# picoKey_2304.net
KiCad netlist of a schematic drawn in EAGLE
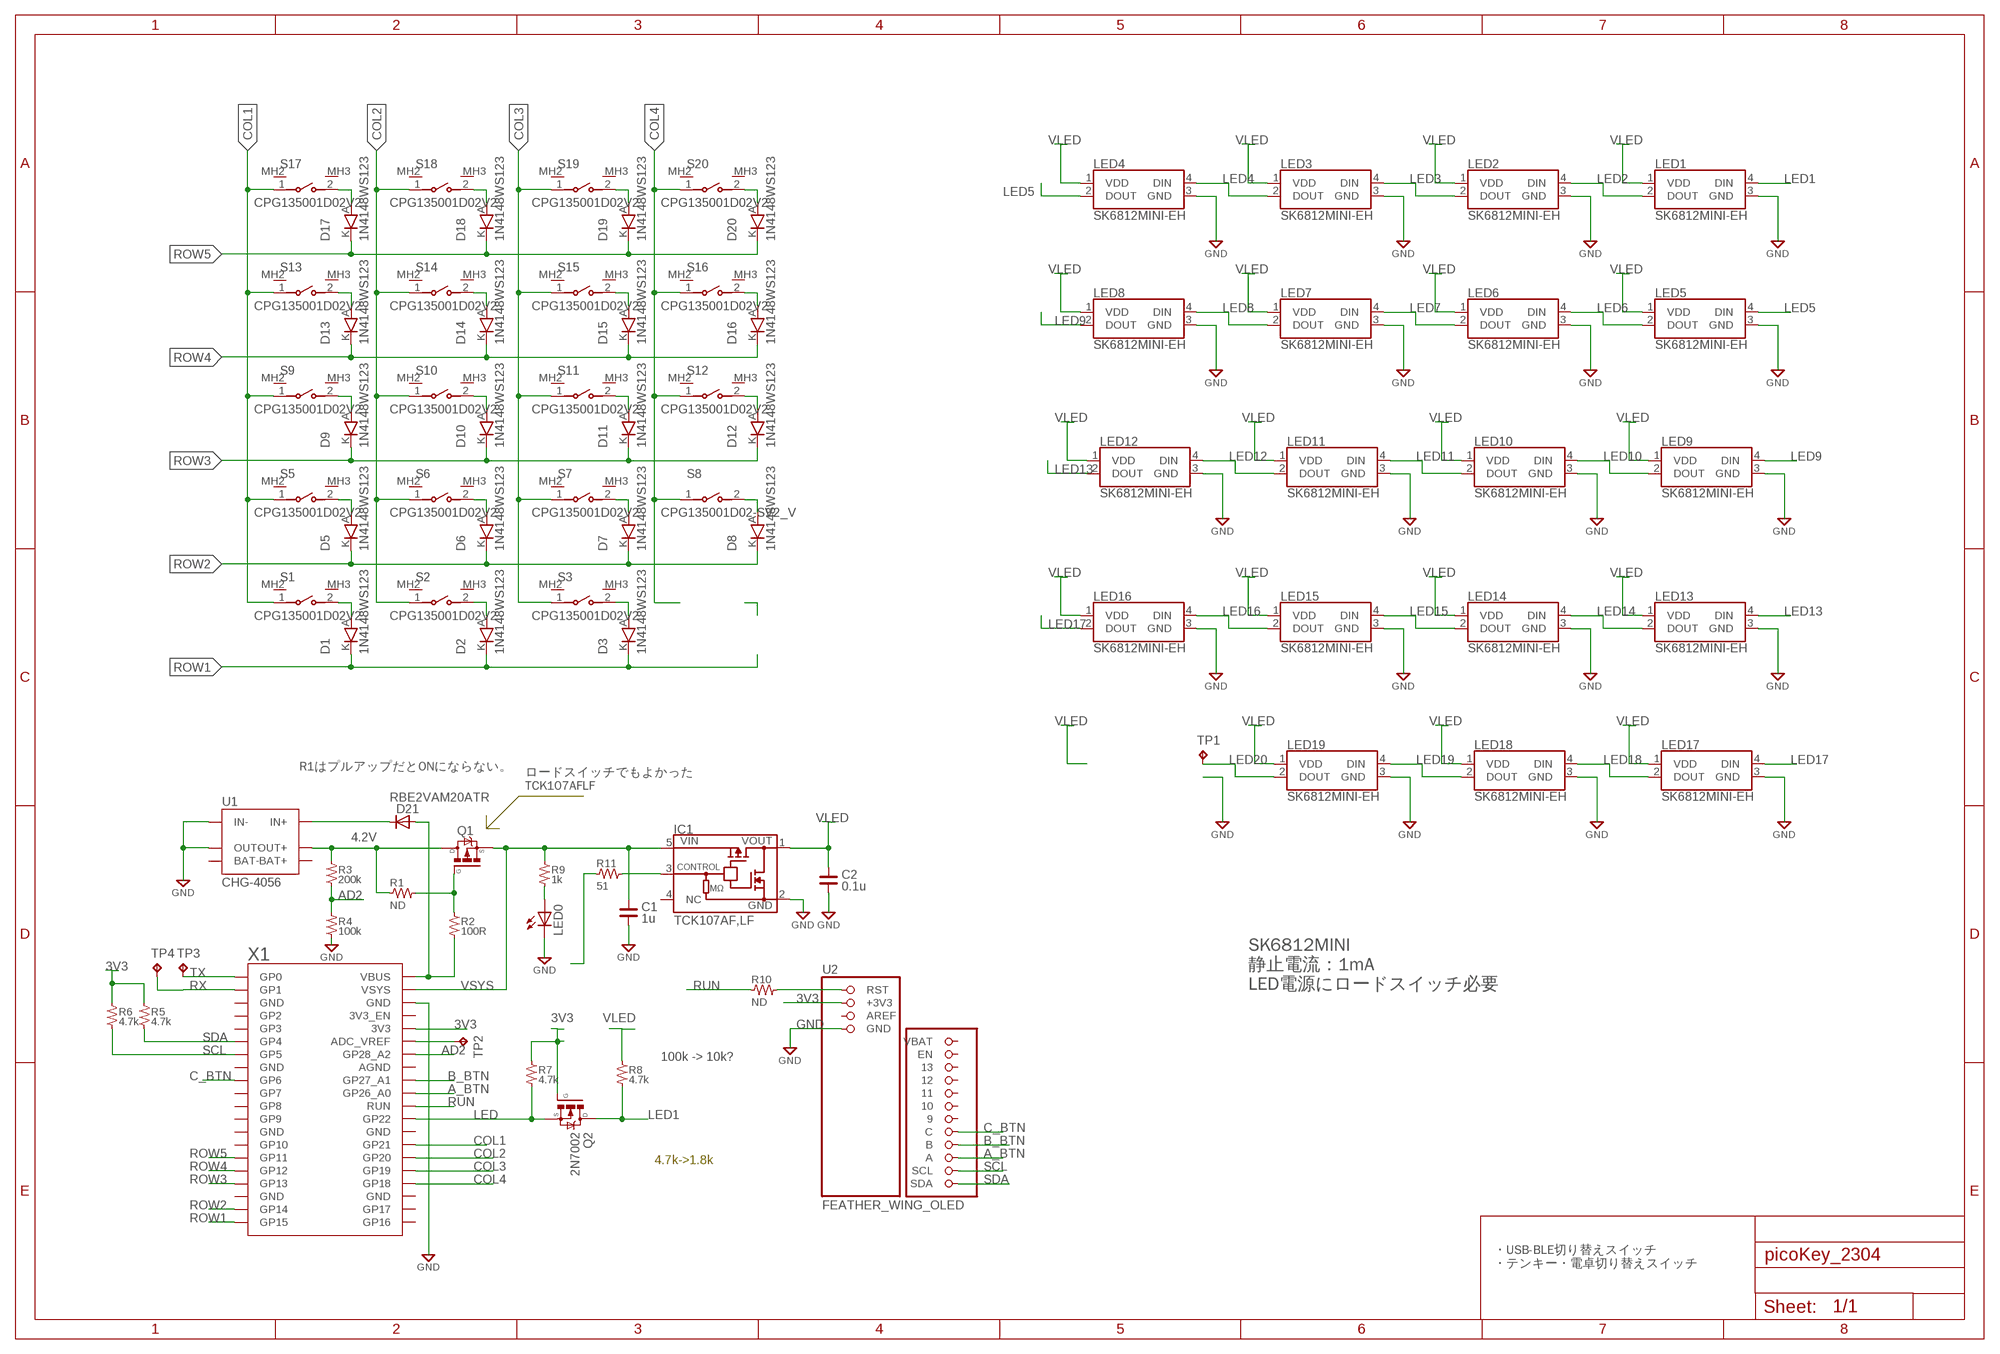
[diagram p0: schematic, sheet 1]

(export (version "E")
  (design (tool "Eeschema 10.0.6"))
  (components
    (comp (ref "C1")
      (value "1u")
      (footprint "eagle-import:C0603")
      (libsource (lib "eagle-import") (part "C_0603"))
    )
    (comp (ref "C2")
      (value "0.1u")
      (footprint "eagle-import:C0603")
      (libsource (lib "eagle-import") (part "C_0603"))
    )
    (comp (ref "D1")
      (value "1N4148WS123")
      (footprint "eagle-import:SOD-123")
      (libsource (lib "eagle-import") (part "1N4148WS123"))
    )
    (comp (ref "D2")
      (value "1N4148WS123")
      (footprint "eagle-import:SOD-123")
      (libsource (lib "eagle-import") (part "1N4148WS123"))
    )
    (comp (ref "D3")
      (value "1N4148WS123")
      (footprint "eagle-import:SOD-123")
      (libsource (lib "eagle-import") (part "1N4148WS123"))
    )
    (comp (ref "D5")
      (value "1N4148WS123")
      (footprint "eagle-import:SOD-123")
      (libsource (lib "eagle-import") (part "1N4148WS123"))
    )
    (comp (ref "D6")
      (value "1N4148WS123")
      (footprint "eagle-import:SOD-123")
      (libsource (lib "eagle-import") (part "1N4148WS123"))
    )
    (comp (ref "D7")
      (value "1N4148WS123")
      (footprint "eagle-import:SOD-123")
      (libsource (lib "eagle-import") (part "1N4148WS123"))
    )
    (comp (ref "D8")
      (value "1N4148WS123")
      (footprint "eagle-import:SOD-123")
      (libsource (lib "eagle-import") (part "1N4148WS123"))
    )
    (comp (ref "D9")
      (value "1N4148WS123")
      (footprint "eagle-import:SOD-123")
      (libsource (lib "eagle-import") (part "1N4148WS123"))
    )
    (comp (ref "D10")
      (value "1N4148WS123")
      (footprint "eagle-import:SOD-123")
      (libsource (lib "eagle-import") (part "1N4148WS123"))
    )
    (comp (ref "D11")
      (value "1N4148WS123")
      (footprint "eagle-import:SOD-123")
      (libsource (lib "eagle-import") (part "1N4148WS123"))
    )
    (comp (ref "D12")
      (value "1N4148WS123")
      (footprint "eagle-import:SOD-123")
      (libsource (lib "eagle-import") (part "1N4148WS123"))
    )
    (comp (ref "D13")
      (value "1N4148WS123")
      (footprint "eagle-import:SOD-123")
      (libsource (lib "eagle-import") (part "1N4148WS123"))
    )
    (comp (ref "D14")
      (value "1N4148WS123")
      (footprint "eagle-import:SOD-123")
      (libsource (lib "eagle-import") (part "1N4148WS123"))
    )
    (comp (ref "D15")
      (value "1N4148WS123")
      (footprint "eagle-import:SOD-123")
      (libsource (lib "eagle-import") (part "1N4148WS123"))
    )
    (comp (ref "D16")
      (value "1N4148WS123")
      (footprint "eagle-import:SOD-123")
      (libsource (lib "eagle-import") (part "1N4148WS123"))
    )
    (comp (ref "D17")
      (value "1N4148WS123")
      (footprint "eagle-import:SOD-123")
      (libsource (lib "eagle-import") (part "1N4148WS123"))
    )
    (comp (ref "D18")
      (value "1N4148WS123")
      (footprint "eagle-import:SOD-123")
      (libsource (lib "eagle-import") (part "1N4148WS123"))
    )
    (comp (ref "D19")
      (value "1N4148WS123")
      (footprint "eagle-import:SOD-123")
      (libsource (lib "eagle-import") (part "1N4148WS123"))
    )
    (comp (ref "D20")
      (value "1N4148WS123")
      (footprint "eagle-import:SOD-123")
      (libsource (lib "eagle-import") (part "1N4148WS123"))
    )
    (comp (ref "D21")
      (value "RBE2VAM20ATR")
      (footprint "eagle-import:SOD-123")
      (libsource (lib "eagle-import") (part "DIODE123"))
    )
    (comp (ref "IC1")
      (value "TCK107AF,LF")
      (footprint "eagle-import:SMV_1")
      (fields
        (field (name "ARROW_PART_NUMBER") "TCK106AF,LF")
        (field (name "MOUSER_PART_NUMBER") "757-TCK106AFLF")
      )
      (libsource (lib "eagle-import") (part "TCK107AF,LF"))
    )
    (comp (ref "LED0")
      (value "LEDCHIP-LED0603")
      (footprint "eagle-import:CHIP-LED0603")
      (libsource (lib "eagle-import") (part "LEDCHIP-LED0603"))
    )
    (comp (ref "LED1")
      (value "SK6812MINI-EH")
      (footprint "eagle-import:SK6812MINIE-H")
      (libsource (lib "eagle-import") (part "SK6812MINI-EH"))
    )
    (comp (ref "LED2")
      (value "SK6812MINI-EH")
      (footprint "eagle-import:SK6812MINIE-H")
      (libsource (lib "eagle-import") (part "SK6812MINI-EH"))
    )
    (comp (ref "LED3")
      (value "SK6812MINI-EH")
      (footprint "eagle-import:SK6812MINIE-H")
      (libsource (lib "eagle-import") (part "SK6812MINI-EH"))
    )
    (comp (ref "LED4")
      (value "SK6812MINI-EH")
      (footprint "eagle-import:SK6812MINIE-H")
      (libsource (lib "eagle-import") (part "SK6812MINI-EH"))
    )
    (comp (ref "LED5")
      (value "SK6812MINI-EH")
      (footprint "eagle-import:SK6812MINIE-H")
      (libsource (lib "eagle-import") (part "SK6812MINI-EH"))
    )
    (comp (ref "LED6")
      (value "SK6812MINI-EH")
      (footprint "eagle-import:SK6812MINIE-H")
      (libsource (lib "eagle-import") (part "SK6812MINI-EH"))
    )
    (comp (ref "LED7")
      (value "SK6812MINI-EH")
      (footprint "eagle-import:SK6812MINIE-H")
      (libsource (lib "eagle-import") (part "SK6812MINI-EH"))
    )
    (comp (ref "LED8")
      (value "SK6812MINI-EH")
      (footprint "eagle-import:SK6812MINIE-H")
      (libsource (lib "eagle-import") (part "SK6812MINI-EH"))
    )
    (comp (ref "LED9")
      (value "SK6812MINI-EH")
      (footprint "eagle-import:SK6812MINIE-H")
      (libsource (lib "eagle-import") (part "SK6812MINI-EH"))
    )
    (comp (ref "LED10")
      (value "SK6812MINI-EH")
      (footprint "eagle-import:SK6812MINIE-H")
      (libsource (lib "eagle-import") (part "SK6812MINI-EH"))
    )
    (comp (ref "LED11")
      (value "SK6812MINI-EH")
      (footprint "eagle-import:SK6812MINIE-H")
      (libsource (lib "eagle-import") (part "SK6812MINI-EH"))
    )
    (comp (ref "LED12")
      (value "SK6812MINI-EH")
      (footprint "eagle-import:SK6812MINIE-H")
      (libsource (lib "eagle-import") (part "SK6812MINI-EH"))
    )
    (comp (ref "LED13")
      (value "SK6812MINI-EH")
      (footprint "eagle-import:SK6812MINIE-H")
      (libsource (lib "eagle-import") (part "SK6812MINI-EH"))
    )
    (comp (ref "LED14")
      (value "SK6812MINI-EH")
      (footprint "eagle-import:SK6812MINIE-H")
      (libsource (lib "eagle-import") (part "SK6812MINI-EH"))
    )
    (comp (ref "LED15")
      (value "SK6812MINI-EH")
      (footprint "eagle-import:SK6812MINIE-H")
      (libsource (lib "eagle-import") (part "SK6812MINI-EH"))
    )
    (comp (ref "LED16")
      (value "SK6812MINI-EH")
      (footprint "eagle-import:SK6812MINIE-H")
      (libsource (lib "eagle-import") (part "SK6812MINI-EH"))
    )
    (comp (ref "LED17")
      (value "SK6812MINI-EH")
      (footprint "eagle-import:SK6812MINIE-H")
      (libsource (lib "eagle-import") (part "SK6812MINI-EH"))
    )
    (comp (ref "LED18")
      (value "SK6812MINI-EH")
      (footprint "eagle-import:SK6812MINIE-H")
      (libsource (lib "eagle-import") (part "SK6812MINI-EH"))
    )
    (comp (ref "LED19")
      (value "SK6812MINI-EH")
      (footprint "eagle-import:SK6812MINIE-H")
      (libsource (lib "eagle-import") (part "SK6812MINI-EH"))
    )
    (comp (ref "Q1")
      (value "MOSFET-P")
      (footprint "eagle-import:SOT-23")
      (libsource (lib "eagle-import") (part "MOSFET-P"))
    )
    (comp (ref "Q2")
      (value "2N7002")
      (footprint "eagle-import:SOT-23")
      (libsource (lib "eagle-import") (part "MOSFET-NSOT-23"))
    )
    (comp (ref "R1")
      (value "ND")
      (footprint "eagle-import:R0603")
      (libsource (lib "eagle-import") (part "R_0603"))
    )
    (comp (ref "R2")
      (value "100R")
      (footprint "eagle-import:R0603")
      (libsource (lib "eagle-import") (part "R_0603"))
    )
    (comp (ref "R3")
      (value "200k")
      (footprint "eagle-import:R0603")
      (libsource (lib "eagle-import") (part "R_0603"))
    )
    (comp (ref "R4")
      (value "100k")
      (footprint "eagle-import:R0603")
      (libsource (lib "eagle-import") (part "R_0603"))
    )
    (comp (ref "R5")
      (value "4.7k")
      (footprint "eagle-import:R0603")
      (libsource (lib "eagle-import") (part "R_0603"))
    )
    (comp (ref "R6")
      (value "4.7k")
      (footprint "eagle-import:R0603")
      (libsource (lib "eagle-import") (part "R_0603"))
    )
    (comp (ref "R7")
      (value "4.7k")
      (footprint "eagle-import:R0603")
      (libsource (lib "eagle-import") (part "R_0603"))
    )
    (comp (ref "R8")
      (value "4.7k")
      (footprint "eagle-import:R0603")
      (libsource (lib "eagle-import") (part "R_0603"))
    )
    (comp (ref "R9")
      (value "1k")
      (footprint "eagle-import:R0603")
      (libsource (lib "eagle-import") (part "R_0603"))
    )
    (comp (ref "R10")
      (value "ND")
      (footprint "eagle-import:R0603")
      (libsource (lib "eagle-import") (part "R_0603"))
    )
    (comp (ref "R11")
      (value "51")
      (footprint "eagle-import:R0603")
      (libsource (lib "eagle-import") (part "R_0603"))
    )
    (comp (ref "S1")
      (value "CPG135001D02V2")
      (footprint "eagle-import:KAILH_CHOC_V2")
      (libsource (lib "eagle-import") (part "CPG135001D02V2"))
    )
    (comp (ref "S2")
      (value "CPG135001D02V2")
      (footprint "eagle-import:KAILH_CHOC_V2")
      (libsource (lib "eagle-import") (part "CPG135001D02V2"))
    )
    (comp (ref "S3")
      (value "CPG135001D02V2")
      (footprint "eagle-import:KAILH_CHOC_V2")
      (libsource (lib "eagle-import") (part "CPG135001D02V2"))
    )
    (comp (ref "S5")
      (value "CPG135001D02V2")
      (footprint "eagle-import:KAILH_CHOC_V2")
      (libsource (lib "eagle-import") (part "CPG135001D02V2"))
    )
    (comp (ref "S6")
      (value "CPG135001D02V2")
      (footprint "eagle-import:KAILH_CHOC_V2")
      (libsource (lib "eagle-import") (part "CPG135001D02V2"))
    )
    (comp (ref "S7")
      (value "CPG135001D02V2")
      (footprint "eagle-import:KAILH_CHOC_V2")
      (libsource (lib "eagle-import") (part "CPG135001D02V2"))
    )
    (comp (ref "S8")
      (value "CPG135001D02-SV2_V")
      (footprint "eagle-import:KAILH_CHOC_V2_V")
      (libsource (lib "eagle-import") (part "CPG135001D02-SV2_V"))
    )
    (comp (ref "S9")
      (value "CPG135001D02V2")
      (footprint "eagle-import:KAILH_CHOC_V2")
      (libsource (lib "eagle-import") (part "CPG135001D02V2"))
    )
    (comp (ref "S10")
      (value "CPG135001D02V2")
      (footprint "eagle-import:KAILH_CHOC_V2")
      (libsource (lib "eagle-import") (part "CPG135001D02V2"))
    )
    (comp (ref "S11")
      (value "CPG135001D02V2")
      (footprint "eagle-import:KAILH_CHOC_V2")
      (libsource (lib "eagle-import") (part "CPG135001D02V2"))
    )
    (comp (ref "S12")
      (value "CPG135001D02V2")
      (footprint "eagle-import:KAILH_CHOC_V2")
      (libsource (lib "eagle-import") (part "CPG135001D02V2"))
    )
    (comp (ref "S13")
      (value "CPG135001D02V2")
      (footprint "eagle-import:KAILH_CHOC_V2")
      (libsource (lib "eagle-import") (part "CPG135001D02V2"))
    )
    (comp (ref "S14")
      (value "CPG135001D02V2")
      (footprint "eagle-import:KAILH_CHOC_V2")
      (libsource (lib "eagle-import") (part "CPG135001D02V2"))
    )
    (comp (ref "S15")
      (value "CPG135001D02V2")
      (footprint "eagle-import:KAILH_CHOC_V2")
      (libsource (lib "eagle-import") (part "CPG135001D02V2"))
    )
    (comp (ref "S16")
      (value "CPG135001D02V2")
      (footprint "eagle-import:KAILH_CHOC_V2")
      (libsource (lib "eagle-import") (part "CPG135001D02V2"))
    )
    (comp (ref "S17")
      (value "CPG135001D02V2")
      (footprint "eagle-import:KAILH_CHOC_V2")
      (libsource (lib "eagle-import") (part "CPG135001D02V2"))
    )
    (comp (ref "S18")
      (value "CPG135001D02V2")
      (footprint "eagle-import:KAILH_CHOC_V2")
      (libsource (lib "eagle-import") (part "CPG135001D02V2"))
    )
    (comp (ref "S19")
      (value "CPG135001D02V2")
      (footprint "eagle-import:KAILH_CHOC_V2")
      (libsource (lib "eagle-import") (part "CPG135001D02V2"))
    )
    (comp (ref "S20")
      (value "CPG135001D02V2")
      (footprint "eagle-import:KAILH_CHOC_V2")
      (libsource (lib "eagle-import") (part "CPG135001D02V2"))
    )
    (comp (ref "TP1")
      (value "TPTP06R")
      (footprint "eagle-import:TP06R")
      (libsource (lib "eagle-import") (part "TPTP06R"))
    )
    (comp (ref "TP2")
      (value "TPTP06R")
      (footprint "eagle-import:TP06R")
      (libsource (lib "eagle-import") (part "TPTP06R"))
    )
    (comp (ref "TP3")
      (value "TPTP06R")
      (footprint "eagle-import:TP06R")
      (libsource (lib "eagle-import") (part "TPTP06R"))
    )
    (comp (ref "TP4")
      (value "TPTP06R")
      (footprint "eagle-import:TP06R")
      (libsource (lib "eagle-import") (part "TPTP06R"))
    )
    (comp (ref "U1")
      (value "CHG-4056")
      (footprint "eagle-import:CHG-4056")
      (libsource (lib "eagle-import") (part "CHG-4056"))
    )
    (comp (ref "U2")
      (value "FEATHER_WING_OLED")
      (footprint "eagle-import:FEATHER_WING_OLED")
      (libsource (lib "eagle-import") (part "FEATHER_WING_OLED"))
    )
    (comp (ref "X1")
      (value "RASPBERRYPI_PICO_RPI_PICO_MY-MY")
      (footprint "eagle-import:RASPBERRYPI_PICO_RPI_PICO_MY")
      (libsource (lib "eagle-import") (part "RASPBERRYPI_PICO_RPI_PICO_MY-MY"))
    )
  )
  (nets
    (net (code "1") (name "/3V3") (class "Default")
      (node (ref "Q2") (pin "3") (pinfunction "G_3") (pintype "passive"))
      (node (ref "R5") (pin "2") (pinfunction "2_2") (pintype "passive"))
      (node (ref "R6") (pin "2") (pinfunction "2_2") (pintype "passive"))
      (node (ref "R7") (pin "1") (pinfunction "1_1") (pintype "passive"))
      (node (ref "U2") (pin "15") (pinfunction "+3V3_15") (pintype "passive"))
      (node (ref "X1") (pin "3V3") (pinfunction "3V3_3V3") (pintype "bidirectional"))
    )
    (net (code "2") (name "/4.2V") (class "Default")
      (node (ref "Q1") (pin "2") (pinfunction "D_2") (pintype "passive"))
      (node (ref "R1") (pin "1") (pinfunction "1_1") (pintype "passive"))
      (node (ref "R3") (pin "2") (pinfunction "2_2") (pintype "passive"))
      (node (ref "U1") (pin "OUT+") (pinfunction "OUT+_OUT+") (pintype "bidirectional"))
    )
    (net (code "3") (name "/AD2") (class "Default")
      (node (ref "R3") (pin "1") (pinfunction "1_1") (pintype "passive"))
      (node (ref "R4") (pin "2") (pinfunction "2_2") (pintype "passive"))
      (node (ref "X1") (pin "GP28_A2") (pinfunction "GP28_A2_GP28_A2") (pintype "bidirectional"))
    )
    (net (code "4") (name "/A_BTN") (class "Default")
      (node (ref "U2") (pin "26") (pinfunction "A_26") (pintype "passive"))
      (node (ref "X1") (pin "GP26_A0") (pinfunction "GP26_A0_GP26_A0") (pintype "bidirectional"))
    )
    (net (code "5") (name "/B_BTN") (class "Default")
      (node (ref "U2") (pin "25") (pinfunction "B_25") (pintype "passive"))
      (node (ref "X1") (pin "GP27_A1") (pinfunction "GP27_A1_GP27_A1") (pintype "bidirectional"))
    )
    (net (code "6") (name "/C_BTN") (class "Default")
      (node (ref "U2") (pin "24") (pinfunction "C_24") (pintype "passive"))
      (node (ref "X1") (pin "GP6") (pinfunction "GP6_GP6") (pintype "bidirectional"))
    )
    (net (code "7") (name "/LED") (class "Default")
      (node (ref "Q2") (pin "1") (pinfunction "S_1") (pintype "passive"))
      (node (ref "R7") (pin "2") (pinfunction "2_2") (pintype "passive"))
      (node (ref "X1") (pin "GP22") (pinfunction "GP22_GP22") (pintype "bidirectional"))
    )
    (net (code "8") (name "/LED1") (class "Default")
      (node (ref "LED1") (pin "4") (pinfunction "DIN_4") (pintype "bidirectional"))
      (node (ref "Q2") (pin "2") (pinfunction "D_2") (pintype "passive"))
      (node (ref "R8") (pin "2") (pinfunction "2_2") (pintype "passive"))
    )
    (net (code "9") (name "/LED2") (class "Default")
      (node (ref "LED1") (pin "2") (pinfunction "DOUT_2") (pintype "bidirectional"))
      (node (ref "LED2") (pin "4") (pinfunction "DIN_4") (pintype "bidirectional"))
    )
    (net (code "10") (name "/LED3") (class "Default")
      (node (ref "LED2") (pin "2") (pinfunction "DOUT_2") (pintype "bidirectional"))
      (node (ref "LED3") (pin "4") (pinfunction "DIN_4") (pintype "bidirectional"))
    )
    (net (code "11") (name "/LED4") (class "Default")
      (node (ref "LED3") (pin "2") (pinfunction "DOUT_2") (pintype "bidirectional"))
      (node (ref "LED4") (pin "4") (pinfunction "DIN_4") (pintype "bidirectional"))
    )
    (net (code "12") (name "/LED5") (class "Default")
      (node (ref "LED4") (pin "2") (pinfunction "DOUT_2") (pintype "bidirectional"))
      (node (ref "LED5") (pin "4") (pinfunction "DIN_4") (pintype "bidirectional"))
    )
    (net (code "13") (name "/LED6") (class "Default")
      (node (ref "LED5") (pin "2") (pinfunction "DOUT_2") (pintype "bidirectional"))
      (node (ref "LED6") (pin "4") (pinfunction "DIN_4") (pintype "bidirectional"))
    )
    (net (code "14") (name "/LED7") (class "Default")
      (node (ref "LED6") (pin "2") (pinfunction "DOUT_2") (pintype "bidirectional"))
      (node (ref "LED7") (pin "4") (pinfunction "DIN_4") (pintype "bidirectional"))
    )
    (net (code "15") (name "/LED8") (class "Default")
      (node (ref "LED7") (pin "2") (pinfunction "DOUT_2") (pintype "bidirectional"))
      (node (ref "LED8") (pin "4") (pinfunction "DIN_4") (pintype "bidirectional"))
    )
    (net (code "16") (name "/LED9") (class "Default")
      (node (ref "LED8") (pin "2") (pinfunction "DOUT_2") (pintype "bidirectional"))
      (node (ref "LED9") (pin "4") (pinfunction "DIN_4") (pintype "bidirectional"))
    )
    (net (code "17") (name "/LED10") (class "Default")
      (node (ref "LED10") (pin "4") (pinfunction "DIN_4") (pintype "bidirectional"))
      (node (ref "LED9") (pin "2") (pinfunction "DOUT_2") (pintype "bidirectional"))
    )
    (net (code "18") (name "/LED11") (class "Default")
      (node (ref "LED10") (pin "2") (pinfunction "DOUT_2") (pintype "bidirectional"))
      (node (ref "LED11") (pin "4") (pinfunction "DIN_4") (pintype "bidirectional"))
    )
    (net (code "19") (name "/LED12") (class "Default")
      (node (ref "LED11") (pin "2") (pinfunction "DOUT_2") (pintype "bidirectional"))
      (node (ref "LED12") (pin "4") (pinfunction "DIN_4") (pintype "bidirectional"))
    )
    (net (code "20") (name "/LED13") (class "Default")
      (node (ref "LED12") (pin "2") (pinfunction "DOUT_2") (pintype "bidirectional"))
      (node (ref "LED13") (pin "4") (pinfunction "DIN_4") (pintype "bidirectional"))
    )
    (net (code "21") (name "/LED14") (class "Default")
      (node (ref "LED13") (pin "2") (pinfunction "DOUT_2") (pintype "bidirectional"))
      (node (ref "LED14") (pin "4") (pinfunction "DIN_4") (pintype "bidirectional"))
    )
    (net (code "22") (name "/LED15") (class "Default")
      (node (ref "LED14") (pin "2") (pinfunction "DOUT_2") (pintype "bidirectional"))
      (node (ref "LED15") (pin "4") (pinfunction "DIN_4") (pintype "bidirectional"))
    )
    (net (code "23") (name "/LED16") (class "Default")
      (node (ref "LED15") (pin "2") (pinfunction "DOUT_2") (pintype "bidirectional"))
      (node (ref "LED16") (pin "4") (pinfunction "DIN_4") (pintype "bidirectional"))
    )
    (net (code "24") (name "/LED17") (class "Default")
      (node (ref "LED16") (pin "2") (pinfunction "DOUT_2") (pintype "bidirectional"))
      (node (ref "LED17") (pin "4") (pinfunction "DIN_4") (pintype "bidirectional"))
    )
    (net (code "25") (name "/LED18") (class "Default")
      (node (ref "LED17") (pin "2") (pinfunction "DOUT_2") (pintype "bidirectional"))
      (node (ref "LED18") (pin "4") (pinfunction "DIN_4") (pintype "bidirectional"))
    )
    (net (code "26") (name "/LED19") (class "Default")
      (node (ref "LED18") (pin "2") (pinfunction "DOUT_2") (pintype "bidirectional"))
      (node (ref "LED19") (pin "4") (pinfunction "DIN_4") (pintype "bidirectional"))
    )
    (net (code "27") (name "/LED20") (class "Default")
      (node (ref "LED19") (pin "2") (pinfunction "DOUT_2") (pintype "bidirectional"))
      (node (ref "TP1") (pin "TP") (pinfunction "TP_TP") (pintype "input"))
    )
    (net (code "28") (name "/RUN") (class "Default")
      (node (ref "R10") (pin "1") (pinfunction "1_1") (pintype "passive"))
      (node (ref "X1") (pin "RUN") (pinfunction "RUN_RUN") (pintype "bidirectional"))
    )
    (net (code "29") (name "/RX") (class "Default")
      (node (ref "TP4") (pin "TP") (pinfunction "TP_TP") (pintype "input"))
      (node (ref "X1") (pin "GP1") (pinfunction "GP1_GP1") (pintype "bidirectional"))
    )
    (net (code "30") (name "/SCL") (class "Default")
      (node (ref "R6") (pin "1") (pinfunction "1_1") (pintype "passive"))
      (node (ref "U2") (pin "27") (pinfunction "SCL_27") (pintype "passive"))
      (node (ref "X1") (pin "GP5") (pinfunction "GP5_GP5") (pintype "bidirectional"))
    )
    (net (code "31") (name "/SDA") (class "Default")
      (node (ref "R5") (pin "1") (pinfunction "1_1") (pintype "passive"))
      (node (ref "U2") (pin "28") (pinfunction "SDA_28") (pintype "passive"))
      (node (ref "X1") (pin "GP4") (pinfunction "GP4_GP4") (pintype "bidirectional"))
    )
    (net (code "32") (name "/TX") (class "Default")
      (node (ref "TP3") (pin "TP") (pinfunction "TP_TP") (pintype "input"))
      (node (ref "X1") (pin "GP0") (pinfunction "GP0_GP0") (pintype "bidirectional"))
    )
    (net (code "33") (name "/VLED") (class "Default")
      (node (ref "C2") (pin "2") (pinfunction "2_2") (pintype "passive"))
      (node (ref "IC1") (pin "1") (pinfunction "VOUT_1") (pintype "bidirectional"))
      (node (ref "LED1") (pin "1") (pinfunction "VDD_1") (pintype "bidirectional"))
      (node (ref "LED10") (pin "1") (pinfunction "VDD_1") (pintype "bidirectional"))
      (node (ref "LED11") (pin "1") (pinfunction "VDD_1") (pintype "bidirectional"))
      (node (ref "LED12") (pin "1") (pinfunction "VDD_1") (pintype "bidirectional"))
      (node (ref "LED13") (pin "1") (pinfunction "VDD_1") (pintype "bidirectional"))
      (node (ref "LED14") (pin "1") (pinfunction "VDD_1") (pintype "bidirectional"))
      (node (ref "LED15") (pin "1") (pinfunction "VDD_1") (pintype "bidirectional"))
      (node (ref "LED16") (pin "1") (pinfunction "VDD_1") (pintype "bidirectional"))
      (node (ref "LED17") (pin "1") (pinfunction "VDD_1") (pintype "bidirectional"))
      (node (ref "LED18") (pin "1") (pinfunction "VDD_1") (pintype "bidirectional"))
      (node (ref "LED19") (pin "1") (pinfunction "VDD_1") (pintype "bidirectional"))
      (node (ref "LED2") (pin "1") (pinfunction "VDD_1") (pintype "bidirectional"))
      (node (ref "LED3") (pin "1") (pinfunction "VDD_1") (pintype "bidirectional"))
      (node (ref "LED4") (pin "1") (pinfunction "VDD_1") (pintype "bidirectional"))
      (node (ref "LED5") (pin "1") (pinfunction "VDD_1") (pintype "bidirectional"))
      (node (ref "LED6") (pin "1") (pinfunction "VDD_1") (pintype "bidirectional"))
      (node (ref "LED7") (pin "1") (pinfunction "VDD_1") (pintype "bidirectional"))
      (node (ref "LED8") (pin "1") (pinfunction "VDD_1") (pintype "bidirectional"))
      (node (ref "LED9") (pin "1") (pinfunction "VDD_1") (pintype "bidirectional"))
      (node (ref "R8") (pin "1") (pinfunction "1_1") (pintype "passive"))
    )
    (net (code "34") (name "/VSYS") (class "Default")
      (node (ref "C1") (pin "2") (pinfunction "2_2") (pintype "passive"))
      (node (ref "IC1") (pin "5") (pinfunction "VIN_5") (pintype "bidirectional"))
      (node (ref "Q1") (pin "1") (pinfunction "S_1") (pintype "passive"))
      (node (ref "R9") (pin "1") (pinfunction "1_1") (pintype "passive"))
      (node (ref "X1") (pin "VSYS") (pinfunction "VSYS_VSYS") (pintype "bidirectional"))
    )
    (net (code "35") (name "COL1") (class "Default")
      (node (ref "S1") (pin "1") (pinfunction "1_1") (pintype "bidirectional"))
      (node (ref "S13") (pin "1") (pinfunction "1_1") (pintype "bidirectional"))
      (node (ref "S17") (pin "1") (pinfunction "1_1") (pintype "bidirectional"))
      (node (ref "S5") (pin "1") (pinfunction "1_1") (pintype "bidirectional"))
      (node (ref "S9") (pin "1") (pinfunction "1_1") (pintype "bidirectional"))
      (node (ref "X1") (pin "GP21") (pinfunction "GP21_GP21") (pintype "bidirectional"))
    )
    (net (code "36") (name "COL2") (class "Default")
      (node (ref "S10") (pin "1") (pinfunction "1_1") (pintype "bidirectional"))
      (node (ref "S14") (pin "1") (pinfunction "1_1") (pintype "bidirectional"))
      (node (ref "S18") (pin "1") (pinfunction "1_1") (pintype "bidirectional"))
      (node (ref "S2") (pin "1") (pinfunction "1_1") (pintype "bidirectional"))
      (node (ref "S6") (pin "1") (pinfunction "1_1") (pintype "bidirectional"))
      (node (ref "X1") (pin "GP20") (pinfunction "GP20_GP20") (pintype "bidirectional"))
    )
    (net (code "37") (name "COL3") (class "Default")
      (node (ref "S11") (pin "1") (pinfunction "1_1") (pintype "bidirectional"))
      (node (ref "S15") (pin "1") (pinfunction "1_1") (pintype "bidirectional"))
      (node (ref "S19") (pin "1") (pinfunction "1_1") (pintype "bidirectional"))
      (node (ref "S3") (pin "1") (pinfunction "1_1") (pintype "bidirectional"))
      (node (ref "S7") (pin "1") (pinfunction "1_1") (pintype "bidirectional"))
      (node (ref "X1") (pin "GP19") (pinfunction "GP19_GP19") (pintype "bidirectional"))
    )
    (net (code "38") (name "COL4") (class "Default")
      (node (ref "S12") (pin "1") (pinfunction "1_1") (pintype "bidirectional"))
      (node (ref "S16") (pin "1") (pinfunction "1_1") (pintype "bidirectional"))
      (node (ref "S20") (pin "1") (pinfunction "1_1") (pintype "bidirectional"))
      (node (ref "S8") (pin "1") (pinfunction "1_1") (pintype "bidirectional"))
      (node (ref "X1") (pin "GP18") (pinfunction "GP18_GP18") (pintype "bidirectional"))
    )
    (net (code "39") (name "G") (class "Default")
      (node (ref "C1") (pin "1") (pinfunction "1_1") (pintype "passive"))
      (node (ref "C2") (pin "1") (pinfunction "1_1") (pintype "passive"))
      (node (ref "IC1") (pin "2") (pinfunction "GND_2") (pintype "bidirectional"))
      (node (ref "LED0") (pin "C") (pinfunction "C_C") (pintype "passive"))
      (node (ref "LED1") (pin "3") (pinfunction "GND_3") (pintype "bidirectional"))
      (node (ref "LED10") (pin "3") (pinfunction "GND_3") (pintype "bidirectional"))
      (node (ref "LED11") (pin "3") (pinfunction "GND_3") (pintype "bidirectional"))
      (node (ref "LED12") (pin "3") (pinfunction "GND_3") (pintype "bidirectional"))
      (node (ref "LED13") (pin "3") (pinfunction "GND_3") (pintype "bidirectional"))
      (node (ref "LED14") (pin "3") (pinfunction "GND_3") (pintype "bidirectional"))
      (node (ref "LED15") (pin "3") (pinfunction "GND_3") (pintype "bidirectional"))
      (node (ref "LED16") (pin "3") (pinfunction "GND_3") (pintype "bidirectional"))
      (node (ref "LED17") (pin "3") (pinfunction "GND_3") (pintype "bidirectional"))
      (node (ref "LED18") (pin "3") (pinfunction "GND_3") (pintype "bidirectional"))
      (node (ref "LED19") (pin "3") (pinfunction "GND_3") (pintype "bidirectional"))
      (node (ref "LED2") (pin "3") (pinfunction "GND_3") (pintype "bidirectional"))
      (node (ref "LED3") (pin "3") (pinfunction "GND_3") (pintype "bidirectional"))
      (node (ref "LED4") (pin "3") (pinfunction "GND_3") (pintype "bidirectional"))
      (node (ref "LED5") (pin "3") (pinfunction "GND_3") (pintype "bidirectional"))
      (node (ref "LED6") (pin "3") (pinfunction "GND_3") (pintype "bidirectional"))
      (node (ref "LED7") (pin "3") (pinfunction "GND_3") (pintype "bidirectional"))
      (node (ref "LED8") (pin "3") (pinfunction "GND_3") (pintype "bidirectional"))
      (node (ref "LED9") (pin "3") (pinfunction "GND_3") (pintype "bidirectional"))
      (node (ref "R4") (pin "1") (pinfunction "1_1") (pintype "passive"))
      (node (ref "U1") (pin "IN-") (pinfunction "IN-_IN-") (pintype "bidirectional"))
      (node (ref "U1") (pin "OUT-") (pinfunction "OUT-_OUT-") (pintype "bidirectional"))
      (node (ref "U2") (pin "13") (pinfunction "GND_13") (pintype "passive"))
      (node (ref "X1") (pin "GND@8") (pinfunction "GND_GND@8") (pintype "bidirectional"))
    )
    (net (code "40") (name "Net-(D1-PadA)") (class "Default")
      (node (ref "D1") (pin "A") (pinfunction "A_A") (pintype "bidirectional"))
      (node (ref "S1") (pin "2") (pinfunction "2_2") (pintype "bidirectional"))
    )
    (net (code "41") (name "Net-(D2-PadA)") (class "Default")
      (node (ref "D2") (pin "A") (pinfunction "A_A") (pintype "bidirectional"))
      (node (ref "S2") (pin "2") (pinfunction "2_2") (pintype "bidirectional"))
    )
    (net (code "42") (name "Net-(D3-PadA)") (class "Default")
      (node (ref "D3") (pin "A") (pinfunction "A_A") (pintype "bidirectional"))
      (node (ref "S3") (pin "2") (pinfunction "2_2") (pintype "bidirectional"))
    )
    (net (code "43") (name "Net-(D5-PadA)") (class "Default")
      (node (ref "D5") (pin "A") (pinfunction "A_A") (pintype "bidirectional"))
      (node (ref "S5") (pin "2") (pinfunction "2_2") (pintype "bidirectional"))
    )
    (net (code "44") (name "Net-(D6-PadA)") (class "Default")
      (node (ref "D6") (pin "A") (pinfunction "A_A") (pintype "bidirectional"))
      (node (ref "S6") (pin "2") (pinfunction "2_2") (pintype "bidirectional"))
    )
    (net (code "45") (name "Net-(D7-PadA)") (class "Default")
      (node (ref "D7") (pin "A") (pinfunction "A_A") (pintype "bidirectional"))
      (node (ref "S7") (pin "2") (pinfunction "2_2") (pintype "bidirectional"))
    )
    (net (code "46") (name "Net-(D8-PadA)") (class "Default")
      (node (ref "D8") (pin "A") (pinfunction "A_A") (pintype "bidirectional"))
      (node (ref "S8") (pin "2") (pinfunction "2_2") (pintype "bidirectional"))
    )
    (net (code "47") (name "Net-(D9-PadA)") (class "Default")
      (node (ref "D9") (pin "A") (pinfunction "A_A") (pintype "bidirectional"))
      (node (ref "S9") (pin "2") (pinfunction "2_2") (pintype "bidirectional"))
    )
    (net (code "48") (name "Net-(D10-PadA)") (class "Default")
      (node (ref "D10") (pin "A") (pinfunction "A_A") (pintype "bidirectional"))
      (node (ref "S10") (pin "2") (pinfunction "2_2") (pintype "bidirectional"))
    )
    (net (code "49") (name "Net-(D11-PadA)") (class "Default")
      (node (ref "D11") (pin "A") (pinfunction "A_A") (pintype "bidirectional"))
      (node (ref "S11") (pin "2") (pinfunction "2_2") (pintype "bidirectional"))
    )
    (net (code "50") (name "Net-(D12-PadA)") (class "Default")
      (node (ref "D12") (pin "A") (pinfunction "A_A") (pintype "bidirectional"))
      (node (ref "S12") (pin "2") (pinfunction "2_2") (pintype "bidirectional"))
    )
    (net (code "51") (name "Net-(D13-PadA)") (class "Default")
      (node (ref "D13") (pin "A") (pinfunction "A_A") (pintype "bidirectional"))
      (node (ref "S13") (pin "2") (pinfunction "2_2") (pintype "bidirectional"))
    )
    (net (code "52") (name "Net-(D14-PadA)") (class "Default")
      (node (ref "D14") (pin "A") (pinfunction "A_A") (pintype "bidirectional"))
      (node (ref "S14") (pin "2") (pinfunction "2_2") (pintype "bidirectional"))
    )
    (net (code "53") (name "Net-(D15-PadA)") (class "Default")
      (node (ref "D15") (pin "A") (pinfunction "A_A") (pintype "bidirectional"))
      (node (ref "S15") (pin "2") (pinfunction "2_2") (pintype "bidirectional"))
    )
    (net (code "54") (name "Net-(D16-PadA)") (class "Default")
      (node (ref "D16") (pin "A") (pinfunction "A_A") (pintype "bidirectional"))
      (node (ref "S16") (pin "2") (pinfunction "2_2") (pintype "bidirectional"))
    )
    (net (code "55") (name "Net-(D17-PadA)") (class "Default")
      (node (ref "D17") (pin "A") (pinfunction "A_A") (pintype "bidirectional"))
      (node (ref "S17") (pin "2") (pinfunction "2_2") (pintype "bidirectional"))
    )
    (net (code "56") (name "Net-(D18-PadA)") (class "Default")
      (node (ref "D18") (pin "A") (pinfunction "A_A") (pintype "bidirectional"))
      (node (ref "S18") (pin "2") (pinfunction "2_2") (pintype "bidirectional"))
    )
    (net (code "57") (name "Net-(D19-PadA)") (class "Default")
      (node (ref "D19") (pin "A") (pinfunction "A_A") (pintype "bidirectional"))
      (node (ref "S19") (pin "2") (pinfunction "2_2") (pintype "bidirectional"))
    )
    (net (code "58") (name "Net-(D20-PadA)") (class "Default")
      (node (ref "D20") (pin "A") (pinfunction "A_A") (pintype "bidirectional"))
      (node (ref "S20") (pin "2") (pinfunction "2_2") (pintype "bidirectional"))
    )
    (net (code "59") (name "Net-(D21-C)") (class "Default")
      (node (ref "D21") (pin "K") (pinfunction "C_K") (pintype "passive"))
      (node (ref "U1") (pin "IN+") (pinfunction "IN+_IN+") (pintype "bidirectional"))
    )
    (net (code "60") (name "Net-(D21-PadA)") (class "Default")
      (node (ref "D21") (pin "A") (pinfunction "A_A") (pintype "passive"))
      (node (ref "R2") (pin "2") (pinfunction "2_2") (pintype "passive"))
      (node (ref "X1") (pin "VBUS") (pinfunction "VBUS_VBUS") (pintype "bidirectional"))
    )
    (net (code "61") (name "Net-(IC1-CONTROL)") (class "Default")
      (node (ref "IC1") (pin "3") (pinfunction "CONTROL_3") (pintype "bidirectional"))
      (node (ref "R11") (pin "2") (pinfunction "2_2") (pintype "passive"))
    )
    (net (code "62") (name "Net-(LED0-PadA)") (class "Default")
      (node (ref "LED0") (pin "A") (pinfunction "A_A") (pintype "passive"))
      (node (ref "R9") (pin "2") (pinfunction "2_2") (pintype "passive"))
    )
    (net (code "63") (name "Net-(Q1-G)") (class "Default")
      (node (ref "Q1") (pin "3") (pinfunction "G_3") (pintype "passive"))
      (node (ref "R1") (pin "2") (pinfunction "2_2") (pintype "passive"))
      (node (ref "R2") (pin "1") (pinfunction "1_1") (pintype "passive"))
    )
    (net (code "64") (name "Net-(TP2-PadTP)") (class "Default")
      (node (ref "TP2") (pin "TP") (pinfunction "TP_TP") (pintype "input"))
      (node (ref "X1") (pin "ADC_VREF") (pinfunction "ADC_VREF_ADC_VREF") (pintype "bidirectional"))
    )
    (net (code "65") (name "Net-(U2-RST)") (class "Default")
      (node (ref "R10") (pin "2") (pinfunction "2_2") (pintype "passive"))
      (node (ref "U2") (pin "16") (pinfunction "RST_16") (pintype "passive"))
    )
    (net (code "66") (name "ROW1") (class "Default")
      (node (ref "D1") (pin "K") (pinfunction "K_K") (pintype "bidirectional"))
      (node (ref "D2") (pin "K") (pinfunction "K_K") (pintype "bidirectional"))
      (node (ref "D3") (pin "K") (pinfunction "K_K") (pintype "bidirectional"))
      (node (ref "X1") (pin "GP15") (pinfunction "GP15_GP15") (pintype "bidirectional"))
    )
    (net (code "67") (name "ROW2") (class "Default")
      (node (ref "D5") (pin "K") (pinfunction "K_K") (pintype "bidirectional"))
      (node (ref "D6") (pin "K") (pinfunction "K_K") (pintype "bidirectional"))
      (node (ref "D7") (pin "K") (pinfunction "K_K") (pintype "bidirectional"))
      (node (ref "D8") (pin "K") (pinfunction "K_K") (pintype "bidirectional"))
      (node (ref "X1") (pin "GP14") (pinfunction "GP14_GP14") (pintype "bidirectional"))
    )
    (net (code "68") (name "ROW3") (class "Default")
      (node (ref "D10") (pin "K") (pinfunction "K_K") (pintype "bidirectional"))
      (node (ref "D11") (pin "K") (pinfunction "K_K") (pintype "bidirectional"))
      (node (ref "D12") (pin "K") (pinfunction "K_K") (pintype "bidirectional"))
      (node (ref "D9") (pin "K") (pinfunction "K_K") (pintype "bidirectional"))
      (node (ref "X1") (pin "GP13") (pinfunction "GP13_GP13") (pintype "bidirectional"))
    )
    (net (code "69") (name "ROW4") (class "Default")
      (node (ref "D13") (pin "K") (pinfunction "K_K") (pintype "bidirectional"))
      (node (ref "D14") (pin "K") (pinfunction "K_K") (pintype "bidirectional"))
      (node (ref "D15") (pin "K") (pinfunction "K_K") (pintype "bidirectional"))
      (node (ref "D16") (pin "K") (pinfunction "K_K") (pintype "bidirectional"))
      (node (ref "X1") (pin "GP12") (pinfunction "GP12_GP12") (pintype "bidirectional"))
    )
    (net (code "70") (name "ROW5") (class "Default")
      (node (ref "D17") (pin "K") (pinfunction "K_K") (pintype "bidirectional"))
      (node (ref "D18") (pin "K") (pinfunction "K_K") (pintype "bidirectional"))
      (node (ref "D19") (pin "K") (pinfunction "K_K") (pintype "bidirectional"))
      (node (ref "D20") (pin "K") (pinfunction "K_K") (pintype "bidirectional"))
      (node (ref "X1") (pin "GP11") (pinfunction "GP11_GP11") (pintype "bidirectional"))
    )
    (net (code "71") (name "unconnected-(IC1-NC-Pad4)") (class "Default")
      (node (ref "IC1") (pin "4") (pinfunction "NC_4") (pintype "no_connect"))
    )
    (net (code "72") (name "unconnected-(R11-Pad1)") (class "Default")
      (node (ref "R11") (pin "1") (pinfunction "1_1") (pintype "passive"))
    )
    (net (code "73") (name "unconnected-(S1-MH-PadMH2)") (class "Default")
      (node (ref "S1") (pin "MH2") (pinfunction "MH_MH2") (pintype "bidirectional"))
    )
    (net (code "74") (name "unconnected-(S1-MH-PadMH3)") (class "Default")
      (node (ref "S1") (pin "MH3") (pinfunction "MH_MH3") (pintype "bidirectional"))
    )
    (net (code "75") (name "unconnected-(S2-MH-PadMH2)") (class "Default")
      (node (ref "S2") (pin "MH2") (pinfunction "MH_MH2") (pintype "bidirectional"))
    )
    (net (code "76") (name "unconnected-(S2-MH-PadMH3)") (class "Default")
      (node (ref "S2") (pin "MH3") (pinfunction "MH_MH3") (pintype "bidirectional"))
    )
    (net (code "77") (name "unconnected-(S3-MH-PadMH2)") (class "Default")
      (node (ref "S3") (pin "MH2") (pinfunction "MH_MH2") (pintype "bidirectional"))
    )
    (net (code "78") (name "unconnected-(S3-MH-PadMH3)") (class "Default")
      (node (ref "S3") (pin "MH3") (pinfunction "MH_MH3") (pintype "bidirectional"))
    )
    (net (code "79") (name "unconnected-(S5-MH-PadMH2)") (class "Default")
      (node (ref "S5") (pin "MH2") (pinfunction "MH_MH2") (pintype "bidirectional"))
    )
    (net (code "80") (name "unconnected-(S5-MH-PadMH3)") (class "Default")
      (node (ref "S5") (pin "MH3") (pinfunction "MH_MH3") (pintype "bidirectional"))
    )
    (net (code "81") (name "unconnected-(S6-MH-PadMH2)") (class "Default")
      (node (ref "S6") (pin "MH2") (pinfunction "MH_MH2") (pintype "bidirectional"))
    )
    (net (code "82") (name "unconnected-(S6-MH-PadMH3)") (class "Default")
      (node (ref "S6") (pin "MH3") (pinfunction "MH_MH3") (pintype "bidirectional"))
    )
    (net (code "83") (name "unconnected-(S7-MH-PadMH2)") (class "Default")
      (node (ref "S7") (pin "MH2") (pinfunction "MH_MH2") (pintype "bidirectional"))
    )
    (net (code "84") (name "unconnected-(S7-MH-PadMH3)") (class "Default")
      (node (ref "S7") (pin "MH3") (pinfunction "MH_MH3") (pintype "bidirectional"))
    )
    (net (code "85") (name "unconnected-(S9-MH-PadMH2)") (class "Default")
      (node (ref "S9") (pin "MH2") (pinfunction "MH_MH2") (pintype "bidirectional"))
    )
    (net (code "86") (name "unconnected-(S9-MH-PadMH3)") (class "Default")
      (node (ref "S9") (pin "MH3") (pinfunction "MH_MH3") (pintype "bidirectional"))
    )
    (net (code "87") (name "unconnected-(S10-MH-PadMH2)") (class "Default")
      (node (ref "S10") (pin "MH2") (pinfunction "MH_MH2") (pintype "bidirectional"))
    )
    (net (code "88") (name "unconnected-(S10-MH-PadMH3)") (class "Default")
      (node (ref "S10") (pin "MH3") (pinfunction "MH_MH3") (pintype "bidirectional"))
    )
    (net (code "89") (name "unconnected-(S11-MH-PadMH2)") (class "Default")
      (node (ref "S11") (pin "MH2") (pinfunction "MH_MH2") (pintype "bidirectional"))
    )
    (net (code "90") (name "unconnected-(S11-MH-PadMH3)") (class "Default")
      (node (ref "S11") (pin "MH3") (pinfunction "MH_MH3") (pintype "bidirectional"))
    )
    (net (code "91") (name "unconnected-(S12-MH-PadMH2)") (class "Default")
      (node (ref "S12") (pin "MH2") (pinfunction "MH_MH2") (pintype "bidirectional"))
    )
    (net (code "92") (name "unconnected-(S12-MH-PadMH3)") (class "Default")
      (node (ref "S12") (pin "MH3") (pinfunction "MH_MH3") (pintype "bidirectional"))
    )
    (net (code "93") (name "unconnected-(S13-MH-PadMH2)") (class "Default")
      (node (ref "S13") (pin "MH2") (pinfunction "MH_MH2") (pintype "bidirectional"))
    )
    (net (code "94") (name "unconnected-(S13-MH-PadMH3)") (class "Default")
      (node (ref "S13") (pin "MH3") (pinfunction "MH_MH3") (pintype "bidirectional"))
    )
    (net (code "95") (name "unconnected-(S14-MH-PadMH2)") (class "Default")
      (node (ref "S14") (pin "MH2") (pinfunction "MH_MH2") (pintype "bidirectional"))
    )
    (net (code "96") (name "unconnected-(S14-MH-PadMH3)") (class "Default")
      (node (ref "S14") (pin "MH3") (pinfunction "MH_MH3") (pintype "bidirectional"))
    )
    (net (code "97") (name "unconnected-(S15-MH-PadMH2)") (class "Default")
      (node (ref "S15") (pin "MH2") (pinfunction "MH_MH2") (pintype "bidirectional"))
    )
    (net (code "98") (name "unconnected-(S15-MH-PadMH3)") (class "Default")
      (node (ref "S15") (pin "MH3") (pinfunction "MH_MH3") (pintype "bidirectional"))
    )
    (net (code "99") (name "unconnected-(S16-MH-PadMH2)") (class "Default")
      (node (ref "S16") (pin "MH2") (pinfunction "MH_MH2") (pintype "bidirectional"))
    )
    (net (code "100") (name "unconnected-(S16-MH-PadMH3)") (class "Default")
      (node (ref "S16") (pin "MH3") (pinfunction "MH_MH3") (pintype "bidirectional"))
    )
    (net (code "101") (name "unconnected-(S17-MH-PadMH2)") (class "Default")
      (node (ref "S17") (pin "MH2") (pinfunction "MH_MH2") (pintype "bidirectional"))
    )
    (net (code "102") (name "unconnected-(S17-MH-PadMH3)") (class "Default")
      (node (ref "S17") (pin "MH3") (pinfunction "MH_MH3") (pintype "bidirectional"))
    )
    (net (code "103") (name "unconnected-(S18-MH-PadMH2)") (class "Default")
      (node (ref "S18") (pin "MH2") (pinfunction "MH_MH2") (pintype "bidirectional"))
    )
    (net (code "104") (name "unconnected-(S18-MH-PadMH3)") (class "Default")
      (node (ref "S18") (pin "MH3") (pinfunction "MH_MH3") (pintype "bidirectional"))
    )
    (net (code "105") (name "unconnected-(S19-MH-PadMH2)") (class "Default")
      (node (ref "S19") (pin "MH2") (pinfunction "MH_MH2") (pintype "bidirectional"))
    )
    (net (code "106") (name "unconnected-(S19-MH-PadMH3)") (class "Default")
      (node (ref "S19") (pin "MH3") (pinfunction "MH_MH3") (pintype "bidirectional"))
    )
    (net (code "107") (name "unconnected-(S20-MH-PadMH2)") (class "Default")
      (node (ref "S20") (pin "MH2") (pinfunction "MH_MH2") (pintype "bidirectional"))
    )
    (net (code "108") (name "unconnected-(S20-MH-PadMH3)") (class "Default")
      (node (ref "S20") (pin "MH3") (pinfunction "MH_MH3") (pintype "bidirectional"))
    )
    (net (code "109") (name "unconnected-(U1-PadBAT+)") (class "Default")
      (node (ref "U1") (pin "BAT+") (pinfunction "BAT+_BAT+") (pintype "bidirectional"))
    )
    (net (code "110") (name "unconnected-(U1-PadBAT-)") (class "Default")
      (node (ref "U1") (pin "BAT-") (pinfunction "BAT-_BAT-") (pintype "bidirectional"))
    )
    (net (code "111") (name "unconnected-(U2-9-Pad23)") (class "Default")
      (node (ref "U2") (pin "23") (pinfunction "9_23") (pintype "passive"))
    )
    (net (code "112") (name "unconnected-(U2-10-Pad22)") (class "Default")
      (node (ref "U2") (pin "22") (pinfunction "10_22") (pintype "passive"))
    )
    (net (code "113") (name "unconnected-(U2-11-Pad21)") (class "Default")
      (node (ref "U2") (pin "21") (pinfunction "11_21") (pintype "passive"))
    )
    (net (code "114") (name "unconnected-(U2-12-Pad20)") (class "Default")
      (node (ref "U2") (pin "20") (pinfunction "12_20") (pintype "passive"))
    )
    (net (code "115") (name "unconnected-(U2-13-Pad19)") (class "Default")
      (node (ref "U2") (pin "19") (pinfunction "13_19") (pintype "passive"))
    )
    (net (code "116") (name "unconnected-(U2-AREF-Pad14)") (class "Default")
      (node (ref "U2") (pin "14") (pinfunction "AREF_14") (pintype "passive"))
    )
    (net (code "117") (name "unconnected-(U2-EN-Pad18)") (class "Default")
      (node (ref "U2") (pin "18") (pinfunction "EN_18") (pintype "passive"))
    )
    (net (code "118") (name "unconnected-(U2-VBAT-Pad17)") (class "Default")
      (node (ref "U2") (pin "17") (pinfunction "VBAT_17") (pintype "passive"))
    )
    (net (code "119") (name "unconnected-(X1-GND-PadGND@1)") (class "Default")
      (node (ref "X1") (pin "GND@1") (pinfunction "GND_GND@1") (pintype "bidirectional"))
    )
    (net (code "120") (name "unconnected-(X1-GND-PadGND@2)") (class "Default")
      (node (ref "X1") (pin "GND@2") (pinfunction "GND_GND@2") (pintype "bidirectional"))
    )
    (net (code "121") (name "unconnected-(X1-GND-PadGND@3)") (class "Default")
      (node (ref "X1") (pin "GND@3") (pinfunction "GND_GND@3") (pintype "bidirectional"))
    )
    (net (code "122") (name "unconnected-(X1-GND-PadGND@4)") (class "Default")
      (node (ref "X1") (pin "GND@4") (pinfunction "GND_GND@4") (pintype "bidirectional"))
    )
    (net (code "123") (name "unconnected-(X1-GND-PadGND@6)") (class "Default")
      (node (ref "X1") (pin "GND@6") (pinfunction "GND_GND@6") (pintype "bidirectional"))
    )
    (net (code "124") (name "unconnected-(X1-GND-PadGND@7)") (class "Default")
      (node (ref "X1") (pin "GND@7") (pinfunction "GND_GND@7") (pintype "bidirectional"))
    )
    (net (code "125") (name "unconnected-(X1-Pad3V3_EN)") (class "Default")
      (node (ref "X1") (pin "3V3_EN") (pinfunction "3V3_EN_3V3_EN") (pintype "bidirectional"))
    )
    (net (code "126") (name "unconnected-(X1-PadAGND)") (class "Default")
      (node (ref "X1") (pin "AGND") (pinfunction "AGND_AGND") (pintype "bidirectional"))
    )
    (net (code "127") (name "unconnected-(X1-PadGP2)") (class "Default")
      (node (ref "X1") (pin "GP2") (pinfunction "GP2_GP2") (pintype "bidirectional"))
    )
    (net (code "128") (name "unconnected-(X1-PadGP3)") (class "Default")
      (node (ref "X1") (pin "GP3") (pinfunction "GP3_GP3") (pintype "bidirectional"))
    )
    (net (code "129") (name "unconnected-(X1-PadGP7)") (class "Default")
      (node (ref "X1") (pin "GP7") (pinfunction "GP7_GP7") (pintype "bidirectional"))
    )
    (net (code "130") (name "unconnected-(X1-PadGP8)") (class "Default")
      (node (ref "X1") (pin "GP8") (pinfunction "GP8_GP8") (pintype "bidirectional"))
    )
    (net (code "131") (name "unconnected-(X1-PadGP9)") (class "Default")
      (node (ref "X1") (pin "GP9") (pinfunction "GP9_GP9") (pintype "bidirectional"))
    )
    (net (code "132") (name "unconnected-(X1-PadGP10)") (class "Default")
      (node (ref "X1") (pin "GP10") (pinfunction "GP10_GP10") (pintype "bidirectional"))
    )
    (net (code "133") (name "unconnected-(X1-PadGP16)") (class "Default")
      (node (ref "X1") (pin "GP16") (pinfunction "GP16_GP16") (pintype "bidirectional"))
    )
    (net (code "134") (name "unconnected-(X1-PadGP17)") (class "Default")
      (node (ref "X1") (pin "GP17") (pinfunction "GP17_GP17") (pintype "bidirectional"))
    )
  )
)
